# QDRII_mem.net
KiCad netlist of a schematic drawn in Altium Designer
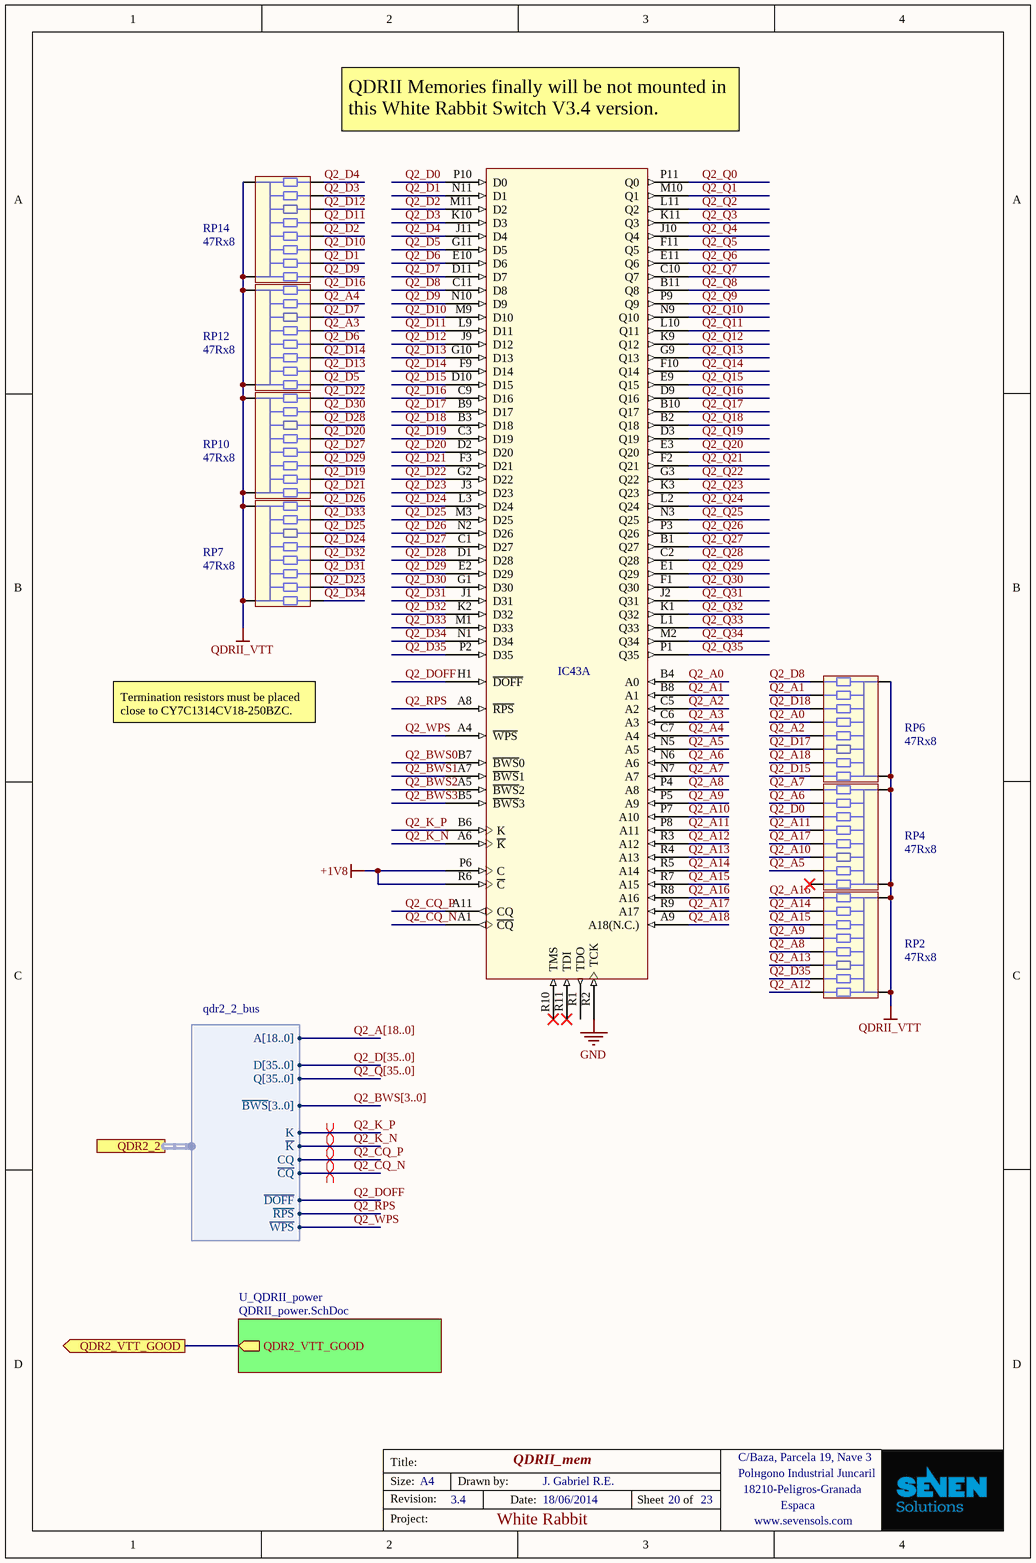
[diagram p0: QDRII_mem.SchDoc]

(export (version "E")
  (design (tool "Eeschema 10.0.6"))
  (components
    (comp (ref "IC43")
      (value "CY7C1314KV18-250BZC")
      (footprint "BGA165C100P11X15_1300X1500X140")
      (description "18-Mbit (512Kx36) QDRII SRAM 2-Word Burst Architecture")
      (libsource (lib "wr_switch") (part "CY7C1314CV18"))
    )
    (comp (ref "RP2")
      (value "47Rx8")
      (footprint "EXBE")
      (description "47R, 62.5mW Chip Resistor Bussed Network")
      (fields (field (name "TOLERANCE") "±5%") (field (name "Comment") "47R x 8"))
      (libsource (lib "wr_switch") (part "EXB-E10C470J"))
    )
    (comp (ref "RP4")
      (value "47Rx8")
      (footprint "EXBE")
      (description "47R, 62.5mW Chip Resistor Bussed Network")
      (fields (field (name "TOLERANCE") "±5%") (field (name "Comment") "47R x 8"))
      (libsource (lib "") (part "EXB-E10C470J_1"))
    )
    (comp (ref "RP6")
      (value "47Rx8")
      (footprint "EXBE")
      (description "47R, 62.5mW Chip Resistor Bussed Network")
      (fields (field (name "TOLERANCE") "±5%") (field (name "Comment") "47R x 8"))
      (libsource (lib "") (part "EXB-E10C470J_2"))
    )
    (comp (ref "RP7")
      (value "47Rx8")
      (footprint "EXBE")
      (description "47R, 62.5mW Chip Resistor Bussed Network")
      (fields (field (name "TOLERANCE") "±5%") (field (name "Comment") "47R x 8"))
      (libsource (lib "") (part "EXB-E10C470J_3"))
    )
    (comp (ref "RP10")
      (value "47Rx8")
      (footprint "EXBE")
      (description "47R, 62.5mW Chip Resistor Bussed Network")
      (fields (field (name "TOLERANCE") "±5%") (field (name "Comment") "47R x 8"))
      (libsource (lib "") (part "EXB-E10C470J_5"))
    )
    (comp (ref "RP12")
      (value "47Rx8")
      (footprint "EXBE")
      (description "47R, 62.5mW Chip Resistor Bussed Network")
      (fields (field (name "TOLERANCE") "±5%") (field (name "Comment") "47R x 8"))
      (libsource (lib "") (part "EXB-E10C470J_4"))
    )
    (comp (ref "RP14")
      (value "47Rx8")
      (footprint "EXBE")
      (description "47R, 62.5mW Chip Resistor Bussed Network")
      (fields (field (name "TOLERANCE") "±5%") (field (name "Comment") "47R x 8"))
      (libsource (lib "") (part "EXB-E10C470J_4"))
    )
  )
  (nets
    (net (code "2") (name "+1V8") (class "Default")
      (node (ref "IC43") (pin "P6") (pinfunction "C_P6") (pintype "input"))
      (node (ref "IC43") (pin "R6") (pinfunction "~{C}_R6") (pintype "input"))
    )
    (net (code "3") (name "/Q2_A0") (class "Default")
      (node (ref "IC43") (pin "B4") (pinfunction "A0_B4") (pintype "input"))
      (node (ref "RP6") (pin "8") (pinfunction "8_8") (pintype "passive"))
    )
    (net (code "4") (name "/Q2_A1") (class "Default")
      (node (ref "IC43") (pin "B8") (pinfunction "A1_B8") (pintype "input"))
      (node (ref "RP6") (pin "10") (pinfunction "10_10") (pintype "passive"))
    )
    (net (code "5") (name "/Q2_A2") (class "Default")
      (node (ref "IC43") (pin "C5") (pinfunction "A2_C5") (pintype "input"))
      (node (ref "RP6") (pin "9") (pinfunction "9_9") (pintype "passive"))
    )
    (net (code "6") (name "/Q2_A3") (class "Default")
      (node (ref "IC43") (pin "C6") (pinfunction "A3_C6") (pintype "input"))
      (node (ref "RP12") (pin "7") (pinfunction "7_7") (pintype "passive"))
    )
    (net (code "7") (name "/Q2_A4") (class "Default")
      (node (ref "IC43") (pin "C7") (pinfunction "A4_C7") (pintype "input"))
      (node (ref "RP12") (pin "9") (pinfunction "9_9") (pintype "passive"))
    )
    (net (code "8") (name "/Q2_A5") (class "Default")
      (node (ref "IC43") (pin "N5") (pinfunction "A5_N5") (pintype "input"))
      (node (ref "RP4") (pin "8") (pinfunction "8_8") (pintype "passive"))
    )
    (net (code "9") (name "/Q2_A6") (class "Default")
      (node (ref "IC43") (pin "N6") (pinfunction "A6_N6") (pintype "input"))
      (node (ref "RP4") (pin "9") (pinfunction "9_9") (pintype "passive"))
    )
    (net (code "10") (name "/Q2_A7") (class "Default")
      (node (ref "IC43") (pin "N7") (pinfunction "A7_N7") (pintype "input"))
      (node (ref "RP4") (pin "10") (pinfunction "10_10") (pintype "passive"))
    )
    (net (code "11") (name "/Q2_A8") (class "Default")
      (node (ref "IC43") (pin "P4") (pinfunction "A8_P4") (pintype "input"))
      (node (ref "RP2") (pin "5") (pinfunction "5_5") (pintype "passive"))
    )
    (net (code "12") (name "/Q2_A9") (class "Default")
      (node (ref "IC43") (pin "P5") (pinfunction "A9_P5") (pintype "input"))
      (node (ref "RP2") (pin "8") (pinfunction "8_8") (pintype "passive"))
    )
    (net (code "13") (name "/Q2_A10") (class "Default")
      (node (ref "IC43") (pin "P7") (pinfunction "A10_P7") (pintype "input"))
      (node (ref "RP4") (pin "2") (pinfunction "2_2") (pintype "passive"))
    )
    (net (code "14") (name "/Q2_A11") (class "Default")
      (node (ref "IC43") (pin "P8") (pinfunction "A11_P8") (pintype "input"))
      (node (ref "RP4") (pin "3") (pinfunction "3_3") (pintype "passive"))
    )
    (net (code "15") (name "/Q2_A12") (class "Default")
      (node (ref "IC43") (pin "R3") (pinfunction "A12_R3") (pintype "input"))
      (node (ref "RP2") (pin "2") (pinfunction "2_2") (pintype "passive"))
    )
    (net (code "16") (name "/Q2_A13") (class "Default")
      (node (ref "IC43") (pin "R4") (pinfunction "A13_R4") (pintype "input"))
      (node (ref "RP2") (pin "4") (pinfunction "4_4") (pintype "passive"))
    )
    (net (code "17") (name "/Q2_A14") (class "Default")
      (node (ref "IC43") (pin "R5") (pinfunction "A14_R5") (pintype "input"))
      (node (ref "RP2") (pin "7") (pinfunction "7_7") (pintype "passive"))
    )
    (net (code "18") (name "/Q2_A15") (class "Default")
      (node (ref "IC43") (pin "R7") (pinfunction "A15_R7") (pintype "input"))
      (node (ref "RP2") (pin "9") (pinfunction "9_9") (pintype "passive"))
    )
    (net (code "19") (name "/Q2_A16") (class "Default")
      (node (ref "IC43") (pin "R8") (pinfunction "A16_R8") (pintype "input"))
      (node (ref "RP2") (pin "10") (pinfunction "10_10") (pintype "passive"))
    )
    (net (code "20") (name "/Q2_A17") (class "Default")
      (node (ref "IC43") (pin "R9") (pinfunction "A17_R9") (pintype "input"))
      (node (ref "RP4") (pin "4") (pinfunction "4_4") (pintype "passive"))
    )
    (net (code "21") (name "/Q2_A18") (class "Default")
      (node (ref "IC43") (pin "A9") (pinfunction "A18(N.C.)_A9") (pintype "input"))
      (node (ref "RP6") (pin "3") (pinfunction "3_3") (pintype "passive"))
    )
    (net (code "22") (name "/Q2_BWS0") (class "Default")
      (node (ref "IC43") (pin "B7") (pinfunction "~{BWS}0_B7") (pintype "input"))
    )
    (net (code "23") (name "/Q2_BWS1") (class "Default")
      (node (ref "IC43") (pin "A7") (pinfunction "~{BWS}1_A7") (pintype "input"))
    )
    (net (code "24") (name "/Q2_BWS2") (class "Default")
      (node (ref "IC43") (pin "A5") (pinfunction "~{BWS}2_A5") (pintype "input"))
    )
    (net (code "25") (name "/Q2_BWS3") (class "Default")
      (node (ref "IC43") (pin "B5") (pinfunction "~{BWS}3_B5") (pintype "input"))
    )
    (net (code "27") (name "/Q2_CQ_N") (class "Default")
      (node (ref "IC43") (pin "A1") (pinfunction "~{CQ}_A1") (pintype "output"))
    )
    (net (code "28") (name "/Q2_CQ_P") (class "Default")
      (node (ref "IC43") (pin "A11") (pinfunction "CQ_A11") (pintype "output"))
    )
    (net (code "29") (name "/Q2_D0") (class "Default")
      (node (ref "IC43") (pin "P10") (pinfunction "D0_P10") (pintype "input"))
      (node (ref "RP4") (pin "5") (pinfunction "5_5") (pintype "passive"))
    )
    (net (code "30") (name "/Q2_D1") (class "Default")
      (node (ref "IC43") (pin "N11") (pinfunction "D1_N11") (pintype "input"))
      (node (ref "RP14") (pin "3") (pinfunction "3_3") (pintype "passive"))
    )
    (net (code "31") (name "/Q2_D2") (class "Default")
      (node (ref "IC43") (pin "M11") (pinfunction "D2_M11") (pintype "input"))
      (node (ref "RP14") (pin "5") (pinfunction "5_5") (pintype "passive"))
    )
    (net (code "32") (name "/Q2_D3") (class "Default")
      (node (ref "IC43") (pin "K10") (pinfunction "D3_K10") (pintype "input"))
      (node (ref "RP14") (pin "9") (pinfunction "9_9") (pintype "passive"))
    )
    (net (code "33") (name "/Q2_D4") (class "Default")
      (node (ref "IC43") (pin "J11") (pinfunction "D4_J11") (pintype "input"))
      (node (ref "RP14") (pin "10") (pinfunction "10_10") (pintype "passive"))
    )
    (net (code "34") (name "/Q2_D5") (class "Default")
      (node (ref "IC43") (pin "G11") (pinfunction "D5_G11") (pintype "input"))
      (node (ref "RP12") (pin "2") (pinfunction "2_2") (pintype "passive"))
    )
    (net (code "35") (name "/Q2_D6") (class "Default")
      (node (ref "IC43") (pin "E10") (pinfunction "D6_E10") (pintype "input"))
      (node (ref "RP12") (pin "5") (pinfunction "5_5") (pintype "passive"))
    )
    (net (code "36") (name "/Q2_D7") (class "Default")
      (node (ref "IC43") (pin "D11") (pinfunction "D7_D11") (pintype "input"))
      (node (ref "RP12") (pin "8") (pinfunction "8_8") (pintype "passive"))
    )
    (net (code "37") (name "/Q2_D8") (class "Default")
      (node (ref "IC43") (pin "C11") (pinfunction "D8_C11") (pintype "input"))
      (node (ref "RP6") (pin "5") (pinfunction "5_5") (pintype "passive"))
    )
    (net (code "38") (name "/Q2_D9") (class "Default")
      (node (ref "IC43") (pin "N10") (pinfunction "D9_N10") (pintype "input"))
      (node (ref "RP14") (pin "2") (pinfunction "2_2") (pintype "passive"))
    )
    (net (code "39") (name "/Q2_D10") (class "Default")
      (node (ref "IC43") (pin "M9") (pinfunction "D10_M9") (pintype "input"))
      (node (ref "RP14") (pin "4") (pinfunction "4_4") (pintype "passive"))
    )
    (net (code "40") (name "/Q2_D11") (class "Default")
      (node (ref "IC43") (pin "L9") (pinfunction "D11_L9") (pintype "input"))
      (node (ref "RP14") (pin "7") (pinfunction "7_7") (pintype "passive"))
    )
    (net (code "41") (name "/Q2_D12") (class "Default")
      (node (ref "IC43") (pin "J9") (pinfunction "D12_J9") (pintype "input"))
      (node (ref "RP14") (pin "8") (pinfunction "8_8") (pintype "passive"))
    )
    (net (code "42") (name "/Q2_D13") (class "Default")
      (node (ref "IC43") (pin "G10") (pinfunction "D13_G10") (pintype "input"))
      (node (ref "RP12") (pin "3") (pinfunction "3_3") (pintype "passive"))
    )
    (net (code "43") (name "/Q2_D14") (class "Default")
      (node (ref "IC43") (pin "F9") (pinfunction "D14_F9") (pintype "input"))
      (node (ref "RP12") (pin "4") (pinfunction "4_4") (pintype "passive"))
    )
    (net (code "44") (name "/Q2_D15") (class "Default")
      (node (ref "IC43") (pin "D10") (pinfunction "D15_D10") (pintype "input"))
      (node (ref "RP6") (pin "4") (pinfunction "4_4") (pintype "passive"))
    )
    (net (code "45") (name "/Q2_D16") (class "Default")
      (node (ref "IC43") (pin "C9") (pinfunction "D16_C9") (pintype "input"))
      (node (ref "RP12") (pin "10") (pinfunction "10_10") (pintype "passive"))
    )
    (net (code "46") (name "/Q2_D17") (class "Default")
      (node (ref "IC43") (pin "B9") (pinfunction "D17_B9") (pintype "input"))
      (node (ref "RP6") (pin "2") (pinfunction "2_2") (pintype "passive"))
    )
    (net (code "47") (name "/Q2_D18") (class "Default")
      (node (ref "IC43") (pin "B3") (pinfunction "D18_B3") (pintype "input"))
      (node (ref "RP6") (pin "7") (pinfunction "7_7") (pintype "passive"))
    )
    (net (code "48") (name "/Q2_D19") (class "Default")
      (node (ref "IC43") (pin "C3") (pinfunction "D19_C3") (pintype "input"))
      (node (ref "RP10") (pin "7") (pinfunction "7_7") (pintype "passive"))
    )
    (net (code "49") (name "/Q2_D20") (class "Default")
      (node (ref "IC43") (pin "D2") (pinfunction "D20_D2") (pintype "input"))
      (node (ref "RP10") (pin "9") (pinfunction "9_9") (pintype "passive"))
    )
    (net (code "50") (name "/Q2_D21") (class "Default")
      (node (ref "IC43") (pin "F3") (pinfunction "D21_F3") (pintype "input"))
      (node (ref "RP10") (pin "3") (pinfunction "3_3") (pintype "passive"))
    )
    (net (code "51") (name "/Q2_D22") (class "Default")
      (node (ref "IC43") (pin "G2") (pinfunction "D22_G2") (pintype "input"))
      (node (ref "RP10") (pin "5") (pinfunction "5_5") (pintype "passive"))
    )
    (net (code "52") (name "/Q2_D23") (class "Default")
      (node (ref "IC43") (pin "J3") (pinfunction "D23_J3") (pintype "input"))
      (node (ref "RP7") (pin "7") (pinfunction "7_7") (pintype "passive"))
    )
    (net (code "53") (name "/Q2_D24") (class "Default")
      (node (ref "IC43") (pin "L3") (pinfunction "D24_L3") (pintype "input"))
      (node (ref "RP7") (pin "10") (pinfunction "10_10") (pintype "passive"))
    )
    (net (code "54") (name "/Q2_D25") (class "Default")
      (node (ref "IC43") (pin "M3") (pinfunction "D25_M3") (pintype "input"))
      (node (ref "RP7") (pin "2") (pinfunction "2_2") (pintype "passive"))
    )
    (net (code "55") (name "/Q2_D26") (class "Default")
      (node (ref "IC43") (pin "N2") (pinfunction "D26_N2") (pintype "input"))
      (node (ref "RP7") (pin "4") (pinfunction "4_4") (pintype "passive"))
    )
    (net (code "56") (name "/Q2_D27") (class "Default")
      (node (ref "IC43") (pin "C1") (pinfunction "D27_C1") (pintype "input"))
      (node (ref "RP10") (pin "8") (pinfunction "8_8") (pintype "passive"))
    )
    (net (code "57") (name "/Q2_D28") (class "Default")
      (node (ref "IC43") (pin "D1") (pinfunction "D28_D1") (pintype "input"))
      (node (ref "RP10") (pin "10") (pinfunction "10_10") (pintype "passive"))
    )
    (net (code "58") (name "/Q2_D29") (class "Default")
      (node (ref "IC43") (pin "E2") (pinfunction "D29_E2") (pintype "input"))
      (node (ref "RP10") (pin "2") (pinfunction "2_2") (pintype "passive"))
    )
    (net (code "59") (name "/Q2_D30") (class "Default")
      (node (ref "IC43") (pin "G1") (pinfunction "D30_G1") (pintype "input"))
      (node (ref "RP10") (pin "4") (pinfunction "4_4") (pintype "passive"))
    )
    (net (code "60") (name "/Q2_D31") (class "Default")
      (node (ref "IC43") (pin "J1") (pinfunction "D31_J1") (pintype "input"))
      (node (ref "RP7") (pin "8") (pinfunction "8_8") (pintype "passive"))
    )
    (net (code "61") (name "/Q2_D32") (class "Default")
      (node (ref "IC43") (pin "K2") (pinfunction "D32_K2") (pintype "input"))
      (node (ref "RP7") (pin "9") (pinfunction "9_9") (pintype "passive"))
    )
    (net (code "62") (name "/Q2_D33") (class "Default")
      (node (ref "IC43") (pin "M1") (pinfunction "D33_M1") (pintype "input"))
      (node (ref "RP7") (pin "3") (pinfunction "3_3") (pintype "passive"))
    )
    (net (code "63") (name "/Q2_D34") (class "Default")
      (node (ref "IC43") (pin "N1") (pinfunction "D34_N1") (pintype "input"))
      (node (ref "RP7") (pin "5") (pinfunction "5_5") (pintype "passive"))
    )
    (net (code "64") (name "/Q2_D35") (class "Default")
      (node (ref "IC43") (pin "P2") (pinfunction "D35_P2") (pintype "input"))
      (node (ref "RP2") (pin "3") (pinfunction "3_3") (pintype "passive"))
    )
    (net (code "65") (name "/Q2_DOFF") (class "Default")
      (node (ref "IC43") (pin "H1") (pinfunction "~{DOFF}_H1") (pintype "input"))
    )
    (net (code "67") (name "/Q2_K_N") (class "Default")
      (node (ref "IC43") (pin "A6") (pinfunction "~{K}_A6") (pintype "input"))
    )
    (net (code "68") (name "/Q2_K_P") (class "Default")
      (node (ref "IC43") (pin "B6") (pinfunction "K_B6") (pintype "input"))
    )
    (net (code "69") (name "/Q2_Q0") (class "Default")
      (node (ref "IC43") (pin "P11") (pinfunction "Q0_P11") (pintype "output"))
    )
    (net (code "70") (name "/Q2_Q1") (class "Default")
      (node (ref "IC43") (pin "M10") (pinfunction "Q1_M10") (pintype "output"))
    )
    (net (code "71") (name "/Q2_Q2") (class "Default")
      (node (ref "IC43") (pin "L11") (pinfunction "Q2_L11") (pintype "output"))
    )
    (net (code "72") (name "/Q2_Q3") (class "Default")
      (node (ref "IC43") (pin "K11") (pinfunction "Q3_K11") (pintype "output"))
    )
    (net (code "73") (name "/Q2_Q4") (class "Default")
      (node (ref "IC43") (pin "J10") (pinfunction "Q4_J10") (pintype "output"))
    )
    (net (code "74") (name "/Q2_Q5") (class "Default")
      (node (ref "IC43") (pin "F11") (pinfunction "Q5_F11") (pintype "output"))
    )
    (net (code "75") (name "/Q2_Q6") (class "Default")
      (node (ref "IC43") (pin "E11") (pinfunction "Q6_E11") (pintype "output"))
    )
    (net (code "76") (name "/Q2_Q7") (class "Default")
      (node (ref "IC43") (pin "C10") (pinfunction "Q7_C10") (pintype "output"))
    )
    (net (code "77") (name "/Q2_Q8") (class "Default")
      (node (ref "IC43") (pin "B11") (pinfunction "Q8_B11") (pintype "output"))
    )
    (net (code "78") (name "/Q2_Q9") (class "Default")
      (node (ref "IC43") (pin "P9") (pinfunction "Q9_P9") (pintype "output"))
    )
    (net (code "79") (name "/Q2_Q10") (class "Default")
      (node (ref "IC43") (pin "N9") (pinfunction "Q10_N9") (pintype "output"))
    )
    (net (code "80") (name "/Q2_Q11") (class "Default")
      (node (ref "IC43") (pin "L10") (pinfunction "Q11_L10") (pintype "output"))
    )
    (net (code "81") (name "/Q2_Q12") (class "Default")
      (node (ref "IC43") (pin "K9") (pinfunction "Q12_K9") (pintype "output"))
    )
    (net (code "82") (name "/Q2_Q13") (class "Default")
      (node (ref "IC43") (pin "G9") (pinfunction "Q13_G9") (pintype "output"))
    )
    (net (code "83") (name "/Q2_Q14") (class "Default")
      (node (ref "IC43") (pin "F10") (pinfunction "Q14_F10") (pintype "output"))
    )
    (net (code "84") (name "/Q2_Q15") (class "Default")
      (node (ref "IC43") (pin "E9") (pinfunction "Q15_E9") (pintype "output"))
    )
    (net (code "85") (name "/Q2_Q16") (class "Default")
      (node (ref "IC43") (pin "D9") (pinfunction "Q16_D9") (pintype "output"))
    )
    (net (code "86") (name "/Q2_Q17") (class "Default")
      (node (ref "IC43") (pin "B10") (pinfunction "Q17_B10") (pintype "output"))
    )
    (net (code "87") (name "/Q2_Q18") (class "Default")
      (node (ref "IC43") (pin "B2") (pinfunction "Q18_B2") (pintype "output"))
    )
    (net (code "88") (name "/Q2_Q19") (class "Default")
      (node (ref "IC43") (pin "D3") (pinfunction "Q19_D3") (pintype "output"))
    )
    (net (code "89") (name "/Q2_Q20") (class "Default")
      (node (ref "IC43") (pin "E3") (pinfunction "Q20_E3") (pintype "output"))
    )
    (net (code "90") (name "/Q2_Q21") (class "Default")
      (node (ref "IC43") (pin "F2") (pinfunction "Q21_F2") (pintype "output"))
    )
    (net (code "91") (name "/Q2_Q22") (class "Default")
      (node (ref "IC43") (pin "G3") (pinfunction "Q22_G3") (pintype "output"))
    )
    (net (code "92") (name "/Q2_Q23") (class "Default")
      (node (ref "IC43") (pin "K3") (pinfunction "Q23_K3") (pintype "output"))
    )
    (net (code "93") (name "/Q2_Q24") (class "Default")
      (node (ref "IC43") (pin "L2") (pinfunction "Q24_L2") (pintype "output"))
    )
    (net (code "94") (name "/Q2_Q25") (class "Default")
      (node (ref "IC43") (pin "N3") (pinfunction "Q25_N3") (pintype "output"))
    )
    (net (code "95") (name "/Q2_Q26") (class "Default")
      (node (ref "IC43") (pin "P3") (pinfunction "Q26_P3") (pintype "output"))
    )
    (net (code "96") (name "/Q2_Q27") (class "Default")
      (node (ref "IC43") (pin "B1") (pinfunction "Q27_B1") (pintype "output"))
    )
    (net (code "97") (name "/Q2_Q28") (class "Default")
      (node (ref "IC43") (pin "C2") (pinfunction "Q28_C2") (pintype "output"))
    )
    (net (code "98") (name "/Q2_Q29") (class "Default")
      (node (ref "IC43") (pin "E1") (pinfunction "Q29_E1") (pintype "output"))
    )
    (net (code "99") (name "/Q2_Q30") (class "Default")
      (node (ref "IC43") (pin "F1") (pinfunction "Q30_F1") (pintype "output"))
    )
    (net (code "100") (name "/Q2_Q31") (class "Default")
      (node (ref "IC43") (pin "J2") (pinfunction "Q31_J2") (pintype "output"))
    )
    (net (code "101") (name "/Q2_Q32") (class "Default")
      (node (ref "IC43") (pin "K1") (pinfunction "Q32_K1") (pintype "output"))
    )
    (net (code "102") (name "/Q2_Q33") (class "Default")
      (node (ref "IC43") (pin "L1") (pinfunction "Q33_L1") (pintype "output"))
    )
    (net (code "103") (name "/Q2_Q34") (class "Default")
      (node (ref "IC43") (pin "M2") (pinfunction "Q34_M2") (pintype "output"))
    )
    (net (code "104") (name "/Q2_Q35") (class "Default")
      (node (ref "IC43") (pin "P1") (pinfunction "Q35_P1") (pintype "output"))
    )
    (net (code "106") (name "/Q2_RPS") (class "Default")
      (node (ref "IC43") (pin "A8") (pinfunction "~{RPS}_A8") (pintype "input"))
    )
    (net (code "107") (name "/Q2_WPS") (class "Default")
      (node (ref "IC43") (pin "A4") (pinfunction "~{WPS}_A4") (pintype "input"))
    )
    (net (code "111") (name "GND") (class "Default")
      (node (ref "IC43") (pin "R2") (pinfunction "TCK_R2") (pintype "input"))
    )
    (net (code "112") (name "QDRII_VTT") (class "Default")
      (node (ref "RP10") (pin "1") (pinfunction "1_1") (pintype "passive"))
      (node (ref "RP10") (pin "6") (pinfunction "6_6") (pintype "passive"))
      (node (ref "RP12") (pin "1") (pinfunction "1_1") (pintype "passive"))
      (node (ref "RP12") (pin "6") (pinfunction "6_6") (pintype "passive"))
      (node (ref "RP14") (pin "1") (pinfunction "1_1") (pintype "passive"))
      (node (ref "RP14") (pin "6") (pinfunction "6_6") (pintype "passive"))
      (node (ref "RP2") (pin "1") (pinfunction "1_1") (pintype "passive"))
      (node (ref "RP2") (pin "6") (pinfunction "6_6") (pintype "passive"))
      (node (ref "RP4") (pin "1") (pinfunction "1_1") (pintype "passive"))
      (node (ref "RP4") (pin "6") (pinfunction "6_6") (pintype "passive"))
      (node (ref "RP6") (pin "1") (pinfunction "1_1") (pintype "passive"))
      (node (ref "RP6") (pin "6") (pinfunction "6_6") (pintype "passive"))
      (node (ref "RP7") (pin "1") (pinfunction "1_1") (pintype "passive"))
      (node (ref "RP7") (pin "6") (pinfunction "6_6") (pintype "passive"))
    )
    (net (code "113") (name "unconnected-(IC43A-TDI-PadR11)") (class "Default")
      (node (ref "IC43") (pin "R11") (pinfunction "TDI_R11") (pintype "input+no_connect"))
    )
    (net (code "114") (name "unconnected-(IC43A-TDO-PadR1)") (class "Default")
      (node (ref "IC43") (pin "R1") (pinfunction "TDO_R1") (pintype "output"))
    )
    (net (code "115") (name "unconnected-(IC43A-TMS-PadR10)") (class "Default")
      (node (ref "IC43") (pin "R10") (pinfunction "TMS_R10") (pintype "input+no_connect"))
    )
    (net (code "116") (name "unconnected-(RP4-Pad7)") (class "Default")
      (node (ref "RP4") (pin "7") (pinfunction "7_7") (pintype "passive+no_connect"))
    )
  )
)
